# femto.net
KiCad netlist of a schematic drawn in EAGLE
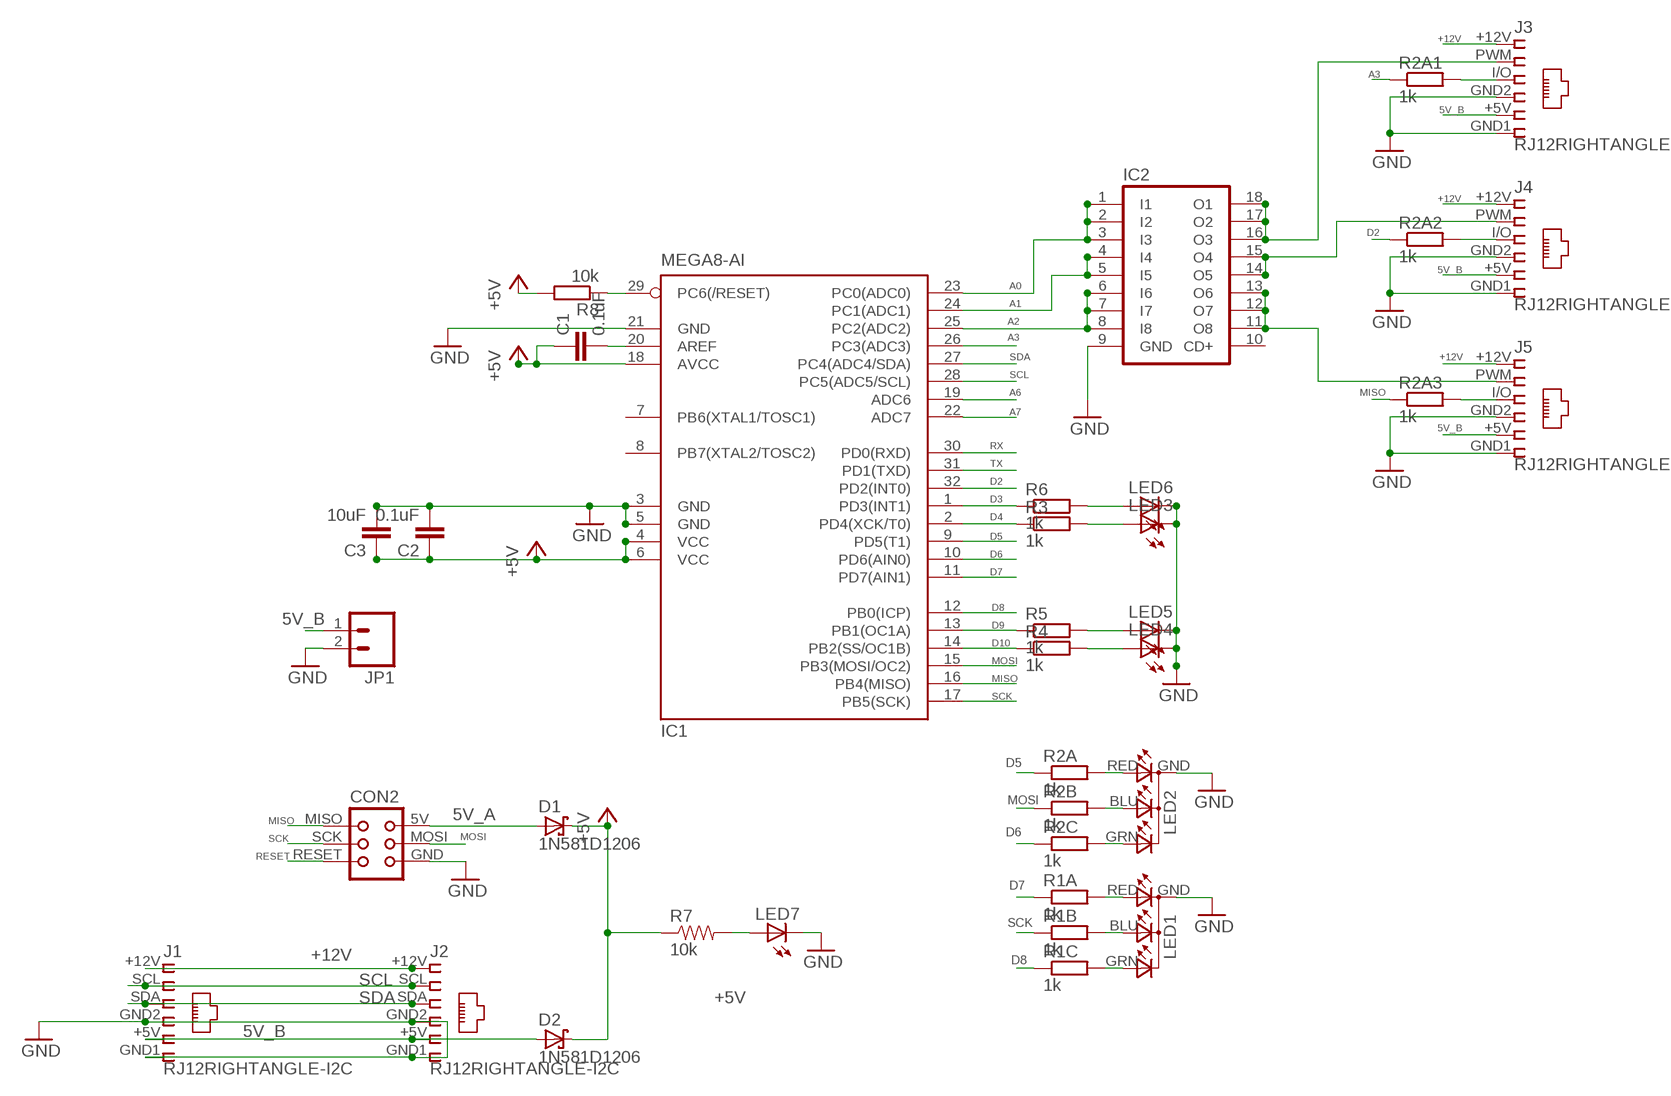
[diagram p0: schematic, sheet 1]

(export (version "E")
  (design (tool "Eeschema 10.0.6"))
  (components
    (comp (ref "C1")
      (value "0.1uF")
      (footprint "eagle-import:C1206")
      (libsource (lib "eagle-import") (part "C-EUC1206"))
    )
    (comp (ref "C2")
      (value "0.1uF")
      (footprint "eagle-import:C1206")
      (libsource (lib "eagle-import") (part "C-EUC1206"))
    )
    (comp (ref "C3")
      (value "10uF")
      (footprint "eagle-import:C1206")
      (libsource (lib "eagle-import") (part "C-EUC1206"))
    )
    (comp (ref "CON2")
      (value "TINYISPTAG")
      (footprint "eagle-import:TC2030-MCP")
      (libsource (lib "eagle-import") (part "TINYISPTAG"))
    )
    (comp (ref "D1")
      (value "1N581D1206")
      (footprint "eagle-import:LED-1206")
      (libsource (lib "eagle-import") (part "1N581D1206"))
    )
    (comp (ref "D2")
      (value "1N581D1206")
      (footprint "eagle-import:LED-1206")
      (libsource (lib "eagle-import") (part "1N581D1206"))
    )
    (comp (ref "IC1")
      (value "MEGA8-AI")
      (footprint "eagle-import:TQFP32-08")
      (fields (field (name "MPN") "ATMEGA8-16AU"))
      (libsource (lib "eagle-import") (part "MEGA8-AI"))
    )
    (comp (ref "IC2")
      (value "ULN2803A")
      (footprint "eagle-import:SO18W")
      (libsource (lib "eagle-import") (part "ULN2803A"))
    )
    (comp (ref "J1")
      (value "RJ12RIGHTANGLE-I2C")
      (footprint "eagle-import:RJ12-RIGHTANGLE-I2C")
      (libsource (lib "eagle-import") (part "RJ12RIGHTANGLE-I2C"))
    )
    (comp (ref "J2")
      (value "RJ12RIGHTANGLE-I2C")
      (footprint "eagle-import:RJ12-RIGHTANGLE-I2C")
      (libsource (lib "eagle-import") (part "RJ12RIGHTANGLE-I2C"))
    )
    (comp (ref "J3")
      (value "RJ12RIGHTANGLE")
      (footprint "eagle-import:RJ12-RIGHTANGLE")
      (libsource (lib "eagle-import") (part "RJ12RIGHTANGLE"))
    )
    (comp (ref "J4")
      (value "RJ12RIGHTANGLE")
      (footprint "eagle-import:RJ12-RIGHTANGLE")
      (libsource (lib "eagle-import") (part "RJ12RIGHTANGLE"))
    )
    (comp (ref "J5")
      (value "RJ12RIGHTANGLE")
      (footprint "eagle-import:RJ12-RIGHTANGLE")
      (libsource (lib "eagle-import") (part "RJ12RIGHTANGLE"))
    )
    (comp (ref "JP1")
      (value "M023.5MM")
      (footprint "eagle-import:SCREWTERMINAL-3.5MM-2")
      (libsource (lib "eagle-import") (part "M023.5MM"))
    )
    (comp (ref "LED1")
      (value "RGB-COMMON-CATHODE")
      (footprint "eagle-import:LED-TRICOLOR-THROUGHHOLE")
      (libsource (lib "eagle-import") (part "RGB-COMMON-CATHODE"))
    )
    (comp (ref "LED2")
      (value "RGB-COMMON-CATHODE")
      (footprint "eagle-import:LED-TRICOLOR-THROUGHHOLE")
      (libsource (lib "eagle-import") (part "RGB-COMMON-CATHODE"))
    )
    (comp (ref "LED3")
      (value "LED3MM")
      (footprint "eagle-import:LED3MM")
      (libsource (lib "eagle-import") (part "lpatiny_LED3MM"))
    )
    (comp (ref "LED4")
      (value "LED3MM")
      (footprint "eagle-import:LED3MM")
      (libsource (lib "eagle-import") (part "lpatiny_LED3MM"))
    )
    (comp (ref "LED5")
      (value "LED3MM")
      (footprint "eagle-import:LED3MM")
      (libsource (lib "eagle-import") (part "lpatiny_LED3MM"))
    )
    (comp (ref "LED6")
      (value "LED3MM")
      (footprint "eagle-import:LED3MM")
      (libsource (lib "eagle-import") (part "lpatiny_LED3MM"))
    )
    (comp (ref "LED7")
      (value "LEDCHIP-LED0603")
      (footprint "eagle-import:CHIP-LED0603")
      (libsource (lib "eagle-import") (part "LEDCHIP-LED0603"))
    )
    (comp (ref "R1A")
      (value "1k")
      (footprint "eagle-import:M1206")
      (libsource (lib "eagle-import") (part "R-EU_M1206"))
    )
    (comp (ref "R1B")
      (value "1k")
      (footprint "eagle-import:M1206")
      (libsource (lib "eagle-import") (part "R-EU_M1206"))
    )
    (comp (ref "R1C")
      (value "1k")
      (footprint "eagle-import:M1206")
      (libsource (lib "eagle-import") (part "R-EU_M1206"))
    )
    (comp (ref "R2A")
      (value "1k")
      (footprint "eagle-import:M1206")
      (libsource (lib "eagle-import") (part "R-EU_M1206"))
    )
    (comp (ref "R2A1")
      (value "1k")
      (footprint "eagle-import:M1206")
      (libsource (lib "eagle-import") (part "R-EU_M1206"))
    )
    (comp (ref "R2A2")
      (value "1k")
      (footprint "eagle-import:M1206")
      (libsource (lib "eagle-import") (part "R-EU_M1206"))
    )
    (comp (ref "R2A3")
      (value "1k")
      (footprint "eagle-import:M1206")
      (libsource (lib "eagle-import") (part "R-EU_M1206"))
    )
    (comp (ref "R2B")
      (value "1k")
      (footprint "eagle-import:M1206")
      (libsource (lib "eagle-import") (part "R-EU_M1206"))
    )
    (comp (ref "R2C")
      (value "1k")
      (footprint "eagle-import:M1206")
      (libsource (lib "eagle-import") (part "R-EU_M1206"))
    )
    (comp (ref "R3")
      (value "1k")
      (footprint "eagle-import:M1206")
      (libsource (lib "eagle-import") (part "R-EU_M1206"))
    )
    (comp (ref "R4")
      (value "1k")
      (footprint "eagle-import:M1206")
      (libsource (lib "eagle-import") (part "R-EU_M1206"))
    )
    (comp (ref "R5")
      (value "1k")
      (footprint "eagle-import:M1206")
      (libsource (lib "eagle-import") (part "R-EU_M1206"))
    )
    (comp (ref "R6")
      (value "1k")
      (footprint "eagle-import:M1206")
      (libsource (lib "eagle-import") (part "R-EU_M1206"))
    )
    (comp (ref "R7")
      (value "10k")
      (footprint "eagle-import:0603-RES")
      (libsource (lib "eagle-import") (part "RESISTOR0603-RES"))
    )
    (comp (ref "R8")
      (value "10k")
      (footprint "eagle-import:M1206")
      (libsource (lib "eagle-import") (part "R-EU_M1206"))
    )
  )
  (nets
    (net (code "1") (name "+5V") (class "Default")
      (node (ref "C1") (pin "1") (pinfunction "1_1") (pintype "passive"))
      (node (ref "C2") (pin "1") (pinfunction "1_1") (pintype "passive"))
      (node (ref "C3") (pin "1") (pinfunction "1_1") (pintype "passive"))
      (node (ref "D1") (pin "C") (pinfunction "C_C") (pintype "passive"))
      (node (ref "D2") (pin "C") (pinfunction "C_C") (pintype "passive"))
      (node (ref "IC1") (pin "18") (pinfunction "AVCC_18") (pintype "power_in"))
      (node (ref "IC1") (pin "4") (pinfunction "VCC_4") (pintype "power_in"))
      (node (ref "IC1") (pin "6") (pinfunction "VCC_6") (pintype "power_in"))
      (node (ref "R7") (pin "1") (pinfunction "1_1") (pintype "passive"))
      (node (ref "R8") (pin "2") (pinfunction "2_2") (pintype "passive"))
    )
    (net (code "2") (name "/+12V") (class "Default")
      (node (ref "J1") (pin "+12V") (pinfunction "1_+12V") (pintype "bidirectional"))
      (node (ref "J2") (pin "+12V") (pinfunction "1_+12V") (pintype "bidirectional"))
      (node (ref "J3") (pin "+12V") (pinfunction "1_+12V") (pintype "bidirectional"))
      (node (ref "J4") (pin "+12V") (pinfunction "1_+12V") (pintype "bidirectional"))
      (node (ref "J5") (pin "+12V") (pinfunction "1_+12V") (pintype "bidirectional"))
    )
    (net (code "3") (name "/5V_A") (class "Default")
      (node (ref "CON2") (pin "5V") (pinfunction "VCC_5V") (pintype "passive"))
      (node (ref "D1") (pin "A") (pinfunction "A_A") (pintype "passive"))
    )
    (net (code "4") (name "/5V_B") (class "Default")
      (node (ref "D2") (pin "A") (pinfunction "A_A") (pintype "passive"))
      (node (ref "J1") (pin "+5V") (pinfunction "5_+5V") (pintype "bidirectional"))
      (node (ref "J2") (pin "+5V") (pinfunction "5_+5V") (pintype "bidirectional"))
      (node (ref "J3") (pin "+5V") (pinfunction "5_+5V") (pintype "bidirectional"))
      (node (ref "J4") (pin "+5V") (pinfunction "5_+5V") (pintype "bidirectional"))
      (node (ref "J5") (pin "+5V") (pinfunction "5_+5V") (pintype "bidirectional"))
      (node (ref "JP1") (pin "1") (pinfunction "1_1") (pintype "passive"))
    )
    (net (code "5") (name "/A0") (class "Default")
      (node (ref "IC1") (pin "23") (pinfunction "PC0(ADC0)_23") (pintype "bidirectional"))
      (node (ref "IC2") (pin "1") (pinfunction "I1_1") (pintype "input"))
      (node (ref "IC2") (pin "2") (pinfunction "I2_2") (pintype "input"))
      (node (ref "IC2") (pin "3") (pinfunction "I3_3") (pintype "input"))
    )
    (net (code "6") (name "/A1") (class "Default")
      (node (ref "IC1") (pin "24") (pinfunction "PC1(ADC1)_24") (pintype "bidirectional"))
      (node (ref "IC2") (pin "4") (pinfunction "I4_4") (pintype "input"))
      (node (ref "IC2") (pin "5") (pinfunction "I5_5") (pintype "input"))
    )
    (net (code "7") (name "/A2") (class "Default")
      (node (ref "IC1") (pin "25") (pinfunction "PC2(ADC2)_25") (pintype "bidirectional"))
      (node (ref "IC2") (pin "6") (pinfunction "I6_6") (pintype "input"))
      (node (ref "IC2") (pin "7") (pinfunction "I7_7") (pintype "input"))
      (node (ref "IC2") (pin "8") (pinfunction "I8_8") (pintype "input"))
    )
    (net (code "8") (name "/A3") (class "Default")
      (node (ref "IC1") (pin "26") (pinfunction "PC3(ADC3)_26") (pintype "bidirectional"))
      (node (ref "R2A1") (pin "1") (pinfunction "1_1") (pintype "passive"))
    )
    (net (code "9") (name "/A6") (class "Default")
      (node (ref "IC1") (pin "19") (pinfunction "ADC6_19") (pintype "bidirectional"))
    )
    (net (code "10") (name "/A7") (class "Default")
      (node (ref "IC1") (pin "22") (pinfunction "ADC7_22") (pintype "bidirectional"))
    )
    (net (code "11") (name "/D2") (class "Default")
      (node (ref "IC1") (pin "32") (pinfunction "PD2(INT0)_32") (pintype "bidirectional"))
      (node (ref "R2A2") (pin "1") (pinfunction "1_1") (pintype "passive"))
    )
    (net (code "12") (name "/D3") (class "Default")
      (node (ref "IC1") (pin "1") (pinfunction "PD3(INT1)_1") (pintype "bidirectional"))
      (node (ref "R6") (pin "1") (pinfunction "1_1") (pintype "passive"))
    )
    (net (code "13") (name "/D4") (class "Default")
      (node (ref "IC1") (pin "2") (pinfunction "PD4(XCK/T0)_2") (pintype "bidirectional"))
      (node (ref "R3") (pin "1") (pinfunction "1_1") (pintype "passive"))
    )
    (net (code "14") (name "/D5") (class "Default")
      (node (ref "IC1") (pin "9") (pinfunction "PD5(T1)_9") (pintype "bidirectional"))
      (node (ref "R2A") (pin "1") (pinfunction "1_1") (pintype "passive"))
    )
    (net (code "15") (name "/D6") (class "Default")
      (node (ref "IC1") (pin "10") (pinfunction "PD6(AIN0)_10") (pintype "bidirectional"))
      (node (ref "R2C") (pin "1") (pinfunction "1_1") (pintype "passive"))
    )
    (net (code "16") (name "/D7") (class "Default")
      (node (ref "IC1") (pin "11") (pinfunction "PD7(AIN1)_11") (pintype "bidirectional"))
      (node (ref "R1A") (pin "1") (pinfunction "1_1") (pintype "passive"))
    )
    (net (code "17") (name "/D8") (class "Default")
      (node (ref "IC1") (pin "12") (pinfunction "PB0(ICP)_12") (pintype "bidirectional"))
      (node (ref "R1C") (pin "1") (pinfunction "1_1") (pintype "passive"))
    )
    (net (code "18") (name "/D9") (class "Default")
      (node (ref "IC1") (pin "13") (pinfunction "PB1(OC1A)_13") (pintype "bidirectional"))
      (node (ref "R5") (pin "1") (pinfunction "1_1") (pintype "passive"))
    )
    (net (code "19") (name "/D10") (class "Default")
      (node (ref "IC1") (pin "14") (pinfunction "PB2(SS/OC1B)_14") (pintype "bidirectional"))
      (node (ref "R4") (pin "1") (pinfunction "1_1") (pintype "passive"))
    )
    (net (code "20") (name "/MISO") (class "Default")
      (node (ref "CON2") (pin "MISO") (pinfunction "MISO_MISO") (pintype "passive"))
      (node (ref "IC1") (pin "16") (pinfunction "PB4(MISO)_16") (pintype "bidirectional"))
      (node (ref "R2A3") (pin "1") (pinfunction "1_1") (pintype "passive"))
    )
    (net (code "21") (name "/MOSI") (class "Default")
      (node (ref "CON2") (pin "MOSI") (pinfunction "MOSI_MOSI") (pintype "passive"))
      (node (ref "IC1") (pin "15") (pinfunction "PB3(MOSI/OC2)_15") (pintype "bidirectional"))
      (node (ref "R2B") (pin "1") (pinfunction "1_1") (pintype "passive"))
    )
    (net (code "22") (name "/RESET") (class "Default")
      (node (ref "CON2") (pin "RESET") (pinfunction "RESET_RESET") (pintype "passive"))
      (node (ref "IC1") (pin "29") (pinfunction "PC6(/RESET)_29") (pintype "bidirectional"))
      (node (ref "R8") (pin "1") (pinfunction "1_1") (pintype "passive"))
    )
    (net (code "23") (name "/RX") (class "Default")
      (node (ref "IC1") (pin "30") (pinfunction "PD0(RXD)_30") (pintype "bidirectional"))
    )
    (net (code "24") (name "/SCK") (class "Default")
      (node (ref "CON2") (pin "SCK") (pinfunction "SCK_SCK") (pintype "passive"))
      (node (ref "IC1") (pin "17") (pinfunction "PB5(SCK)_17") (pintype "bidirectional"))
      (node (ref "R1B") (pin "1") (pinfunction "1_1") (pintype "passive"))
    )
    (net (code "25") (name "/SCL") (class "Default")
      (node (ref "IC1") (pin "28") (pinfunction "PC5(ADC5/SCL)_28") (pintype "bidirectional"))
      (node (ref "J1") (pin "SCL") (pinfunction "2_SCL") (pintype "bidirectional"))
      (node (ref "J2") (pin "SCL") (pinfunction "2_SCL") (pintype "bidirectional"))
    )
    (net (code "26") (name "/SDA") (class "Default")
      (node (ref "IC1") (pin "27") (pinfunction "PC4(ADC4/SDA)_27") (pintype "bidirectional"))
      (node (ref "J1") (pin "SDA") (pinfunction "3_SDA") (pintype "bidirectional"))
      (node (ref "J2") (pin "SDA") (pinfunction "3_SDA") (pintype "bidirectional"))
    )
    (net (code "27") (name "/TX") (class "Default")
      (node (ref "IC1") (pin "31") (pinfunction "PD1(TXD)_31") (pintype "bidirectional"))
    )
    (net (code "28") (name "GND") (class "Default")
      (node (ref "C2") (pin "2") (pinfunction "2_2") (pintype "passive"))
      (node (ref "C3") (pin "2") (pinfunction "2_2") (pintype "passive"))
      (node (ref "CON2") (pin "GND") (pinfunction "GND_GND") (pintype "passive"))
      (node (ref "IC1") (pin "21") (pinfunction "GND_21") (pintype "power_in"))
      (node (ref "IC1") (pin "3") (pinfunction "GND_3") (pintype "power_in"))
      (node (ref "IC1") (pin "5") (pinfunction "GND_5") (pintype "power_in"))
      (node (ref "IC2") (pin "9") (pinfunction "GND_9") (pintype "power_in"))
      (node (ref "J1") (pin "GND1") (pinfunction "6_GND1") (pintype "bidirectional"))
      (node (ref "J1") (pin "GND2") (pinfunction "4_GND2") (pintype "bidirectional"))
      (node (ref "J2") (pin "GND1") (pinfunction "6_GND1") (pintype "bidirectional"))
      (node (ref "J2") (pin "GND2") (pinfunction "4_GND2") (pintype "bidirectional"))
      (node (ref "J3") (pin "GND1") (pinfunction "6_GND1") (pintype "bidirectional"))
      (node (ref "J3") (pin "GND2") (pinfunction "4_GND2") (pintype "bidirectional"))
      (node (ref "J4") (pin "GND1") (pinfunction "6_GND1") (pintype "bidirectional"))
      (node (ref "J4") (pin "GND2") (pinfunction "4_GND2") (pintype "bidirectional"))
      (node (ref "J5") (pin "GND1") (pinfunction "6_GND1") (pintype "bidirectional"))
      (node (ref "J5") (pin "GND2") (pinfunction "4_GND2") (pintype "bidirectional"))
      (node (ref "JP1") (pin "2") (pinfunction "2_2") (pintype "passive"))
      (node (ref "LED1") (pin "GND") (pinfunction "A2_GND") (pintype "passive"))
      (node (ref "LED2") (pin "GND") (pinfunction "A2_GND") (pintype "passive"))
      (node (ref "LED3") (pin "K") (pinfunction "C_K") (pintype "passive"))
      (node (ref "LED4") (pin "K") (pinfunction "C_K") (pintype "passive"))
      (node (ref "LED5") (pin "K") (pinfunction "C_K") (pintype "passive"))
      (node (ref "LED6") (pin "K") (pinfunction "C_K") (pintype "passive"))
      (node (ref "LED7") (pin "C") (pinfunction "C_C") (pintype "passive"))
    )
    (net (code "29") (name "Net-(IC1-AREF)") (class "Default")
      (node (ref "C1") (pin "2") (pinfunction "2_2") (pintype "passive"))
      (node (ref "IC1") (pin "20") (pinfunction "AREF_20") (pintype "passive"))
    )
    (net (code "30") (name "Net-(IC2-O1)") (class "Default")
      (node (ref "IC2") (pin "16") (pinfunction "O3_16") (pintype "open_collector"))
      (node (ref "IC2") (pin "17") (pinfunction "O2_17") (pintype "open_collector"))
      (node (ref "IC2") (pin "18") (pinfunction "O1_18") (pintype "open_collector"))
      (node (ref "J3") (pin "PWM") (pinfunction "2_PWM") (pintype "bidirectional"))
    )
    (net (code "31") (name "Net-(IC2-O4)") (class "Default")
      (node (ref "IC2") (pin "14") (pinfunction "O5_14") (pintype "open_collector"))
      (node (ref "IC2") (pin "15") (pinfunction "O4_15") (pintype "open_collector"))
      (node (ref "J4") (pin "PWM") (pinfunction "2_PWM") (pintype "bidirectional"))
    )
    (net (code "32") (name "Net-(IC2-O6)") (class "Default")
      (node (ref "IC2") (pin "11") (pinfunction "O8_11") (pintype "open_collector"))
      (node (ref "IC2") (pin "12") (pinfunction "O7_12") (pintype "open_collector"))
      (node (ref "IC2") (pin "13") (pinfunction "O6_13") (pintype "open_collector"))
      (node (ref "J5") (pin "PWM") (pinfunction "2_PWM") (pintype "bidirectional"))
    )
    (net (code "33") (name "Net-(J3-3)") (class "Default")
      (node (ref "J3") (pin "I/O") (pinfunction "3_I/O") (pintype "bidirectional"))
      (node (ref "R2A1") (pin "2") (pinfunction "2_2") (pintype "passive"))
    )
    (net (code "34") (name "Net-(J4-3)") (class "Default")
      (node (ref "J4") (pin "I/O") (pinfunction "3_I/O") (pintype "bidirectional"))
      (node (ref "R2A2") (pin "2") (pinfunction "2_2") (pintype "passive"))
    )
    (net (code "35") (name "Net-(J5-3)") (class "Default")
      (node (ref "J5") (pin "I/O") (pinfunction "3_I/O") (pintype "bidirectional"))
      (node (ref "R2A3") (pin "2") (pinfunction "2_2") (pintype "passive"))
    )
    (net (code "36") (name "Net-(LED1-CBLUE)") (class "Default")
      (node (ref "LED1") (pin "BLU") (pinfunction "CBLUE_BLU") (pintype "passive"))
      (node (ref "R1B") (pin "2") (pinfunction "2_2") (pintype "passive"))
    )
    (net (code "37") (name "Net-(LED1-CGREEN)") (class "Default")
      (node (ref "LED1") (pin "GRN") (pinfunction "CGREEN_GRN") (pintype "passive"))
      (node (ref "R1C") (pin "2") (pinfunction "2_2") (pintype "passive"))
    )
    (net (code "38") (name "Net-(LED1-CRED)") (class "Default")
      (node (ref "LED1") (pin "RED") (pinfunction "CRED_RED") (pintype "passive"))
      (node (ref "R1A") (pin "2") (pinfunction "2_2") (pintype "passive"))
    )
    (net (code "39") (name "Net-(LED2-CBLUE)") (class "Default")
      (node (ref "LED2") (pin "BLU") (pinfunction "CBLUE_BLU") (pintype "passive"))
      (node (ref "R2B") (pin "2") (pinfunction "2_2") (pintype "passive"))
    )
    (net (code "40") (name "Net-(LED2-CGREEN)") (class "Default")
      (node (ref "LED2") (pin "GRN") (pinfunction "CGREEN_GRN") (pintype "passive"))
      (node (ref "R2C") (pin "2") (pinfunction "2_2") (pintype "passive"))
    )
    (net (code "41") (name "Net-(LED2-CRED)") (class "Default")
      (node (ref "LED2") (pin "RED") (pinfunction "CRED_RED") (pintype "passive"))
      (node (ref "R2A") (pin "2") (pinfunction "2_2") (pintype "passive"))
    )
    (net (code "42") (name "Net-(LED3-PadA)") (class "Default")
      (node (ref "LED3") (pin "A") (pinfunction "A_A") (pintype "passive"))
      (node (ref "R3") (pin "2") (pinfunction "2_2") (pintype "passive"))
    )
    (net (code "43") (name "Net-(LED4-PadA)") (class "Default")
      (node (ref "LED4") (pin "A") (pinfunction "A_A") (pintype "passive"))
      (node (ref "R4") (pin "2") (pinfunction "2_2") (pintype "passive"))
    )
    (net (code "44") (name "Net-(LED5-PadA)") (class "Default")
      (node (ref "LED5") (pin "A") (pinfunction "A_A") (pintype "passive"))
      (node (ref "R5") (pin "2") (pinfunction "2_2") (pintype "passive"))
    )
    (net (code "45") (name "Net-(LED6-PadA)") (class "Default")
      (node (ref "LED6") (pin "A") (pinfunction "A_A") (pintype "passive"))
      (node (ref "R6") (pin "2") (pinfunction "2_2") (pintype "passive"))
    )
    (net (code "46") (name "Net-(LED7-PadA)") (class "Default")
      (node (ref "LED7") (pin "A") (pinfunction "A_A") (pintype "passive"))
      (node (ref "R7") (pin "2") (pinfunction "2_2") (pintype "passive"))
    )
    (net (code "47") (name "unconnected-(IC1-PB6(XTAL1{slash}TOSC1)-Pad7)") (class "Default")
      (node (ref "IC1") (pin "7") (pinfunction "PB6(XTAL1/TOSC1)_7") (pintype "bidirectional"))
    )
    (net (code "48") (name "unconnected-(IC1-PB7(XTAL2{slash}TOSC2)-Pad8)") (class "Default")
      (node (ref "IC1") (pin "8") (pinfunction "PB7(XTAL2/TOSC2)_8") (pintype "bidirectional"))
    )
    (net (code "49") (name "unconnected-(IC2-CD+-Pad10)") (class "Default")
      (node (ref "IC2") (pin "10") (pinfunction "CD+_10") (pintype "passive"))
    )
  )
)
